# M115C.net
KiCad netlist of a schematic drawn in EAGLE
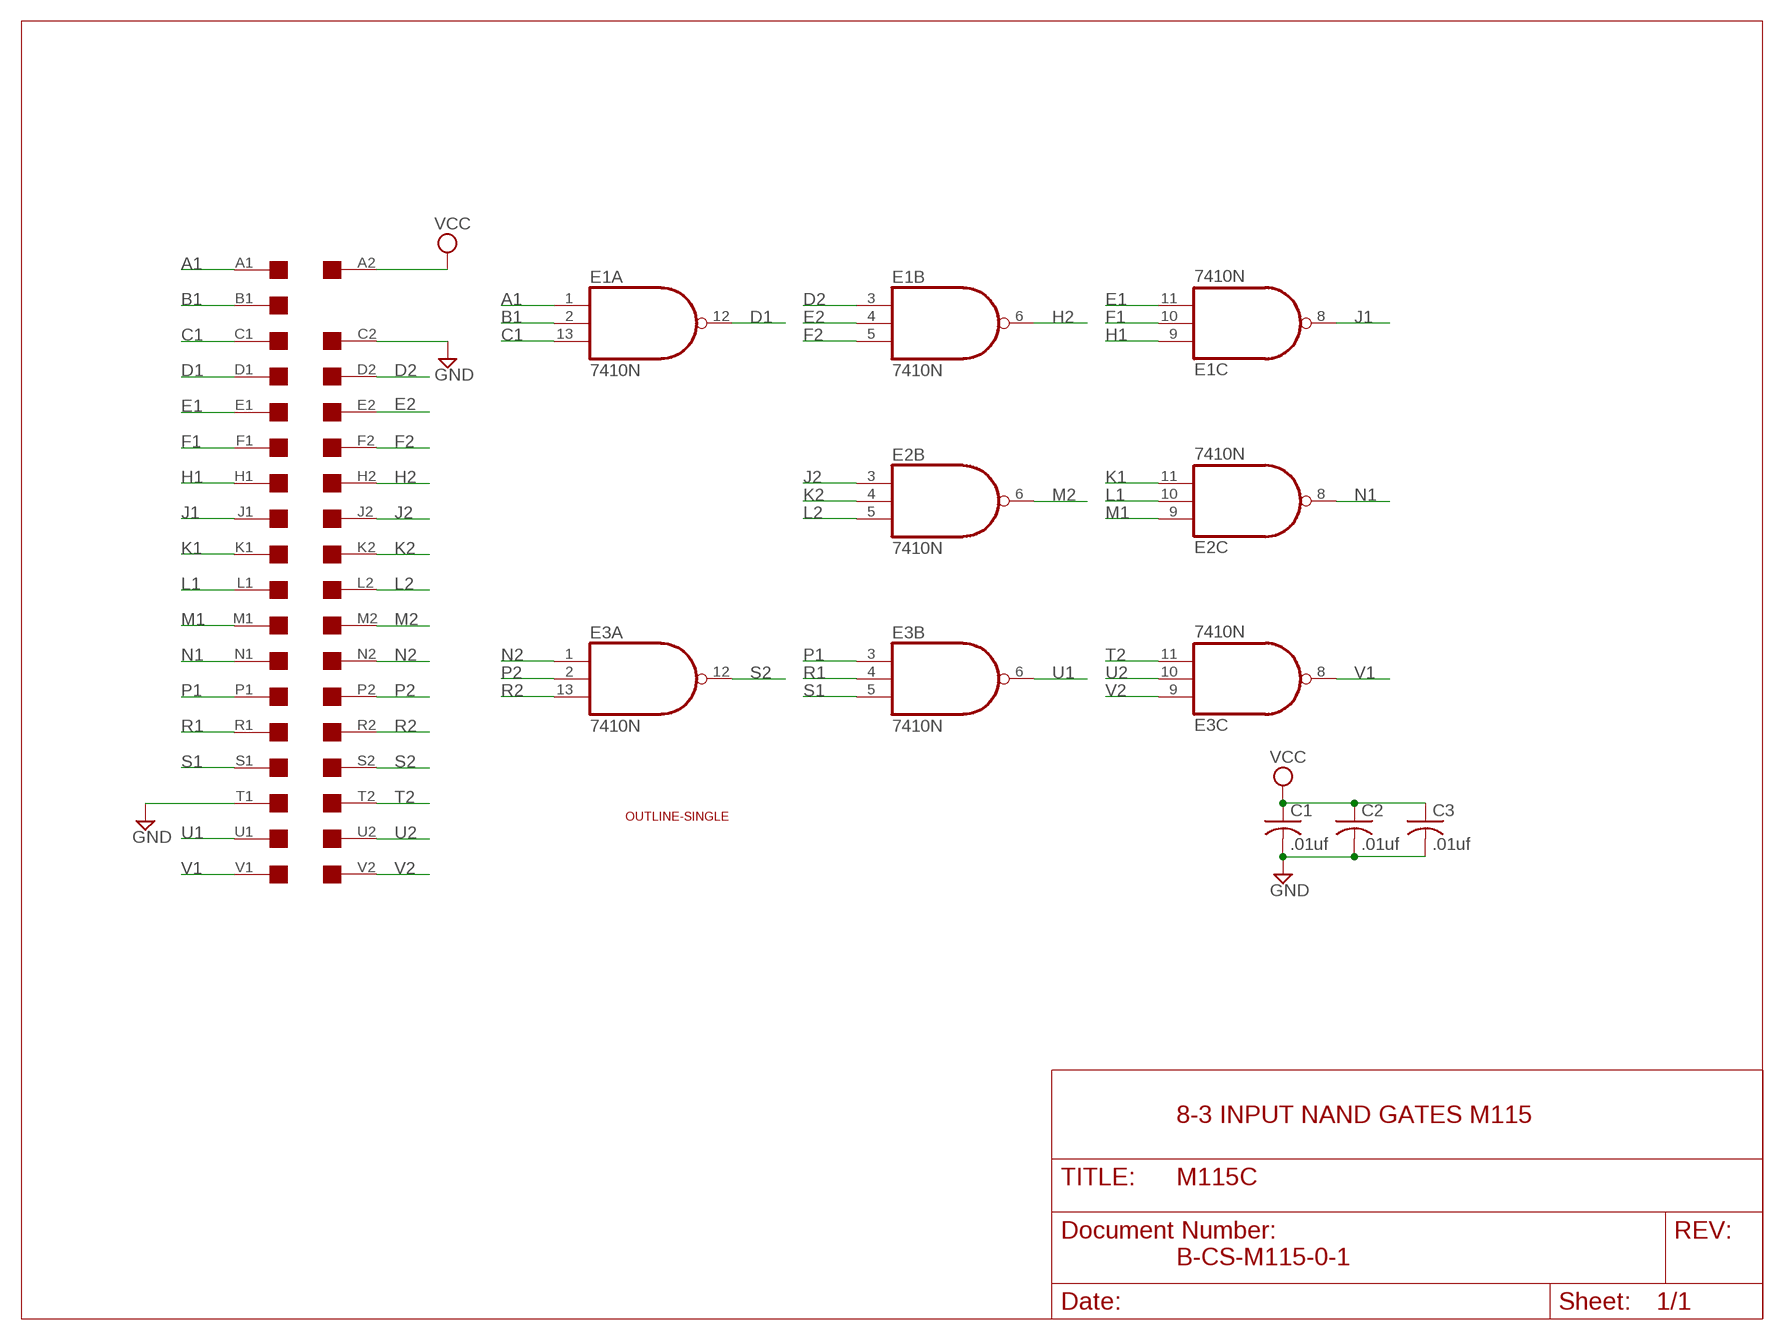
[diagram p0: schematic, sheet 1]

(export (version "E")
  (design (tool "Eeschema 10.0.6"))
  (components
    (comp (ref "C1")
      (value ".01uf")
      (footprint "eagle-import:C050-025X075")
      (libsource (lib "eagle-import") (part "C-US050-025X075"))
    )
    (comp (ref "C2")
      (value ".01uf")
      (footprint "eagle-import:C050-025X075")
      (libsource (lib "eagle-import") (part "C-US050-025X075"))
    )
    (comp (ref "C3")
      (value ".01uf")
      (footprint "eagle-import:C050-025X075")
      (libsource (lib "eagle-import") (part "C-US050-025X075"))
    )
    (comp (ref "E1")
      (value "7410N")
      (footprint "eagle-import:DIL14")
      (libsource (lib "eagle-import") (part "7410N"))
    )
    (comp (ref "E2")
      (value "7410N")
      (footprint "eagle-import:DIL14")
      (libsource (lib "eagle-import") (part "7410N"))
    )
    (comp (ref "E3")
      (value "7410N")
      (footprint "eagle-import:DIL14")
      (libsource (lib "eagle-import") (part "7410N"))
    )
    (comp (ref "U$1")
      (value "SINGLE")
      (footprint "eagle-import:EDGE-CON2")
      (libsource (lib "eagle-import") (part "SINGLE"))
    )
    (comp (ref "U$4")
      (value "OUTLINE-SINGLE")
      (footprint "eagle-import:SINGLE")
      (libsource (lib "eagle-import") (part "OUTLINE-SINGLE"))
    )
  )
  (nets
    (net (code "1") (name "/A1") (class "Default")
      (node (ref "E1") (pin "1") (pinfunction "I0_1") (pintype "input"))
      (node (ref "U$1") (pin "A1") (pinfunction "1_A1") (pintype "bidirectional"))
    )
    (net (code "2") (name "/B1") (class "Default")
      (node (ref "E1") (pin "2") (pinfunction "I1_2") (pintype "input"))
      (node (ref "U$1") (pin "B1") (pinfunction "1_B1") (pintype "bidirectional"))
    )
    (net (code "3") (name "/C1") (class "Default")
      (node (ref "E1") (pin "13") (pinfunction "I2_13") (pintype "input"))
      (node (ref "U$1") (pin "C1") (pinfunction "1_C1") (pintype "bidirectional"))
    )
    (net (code "4") (name "/D1") (class "Default")
      (node (ref "E1") (pin "12") (pinfunction "O_12") (pintype "output"))
      (node (ref "U$1") (pin "D1") (pinfunction "1_D1") (pintype "bidirectional"))
    )
    (net (code "5") (name "/D2") (class "Default")
      (node (ref "E1") (pin "3") (pinfunction "I0_3") (pintype "input"))
      (node (ref "U$1") (pin "D2") (pinfunction "1_D2") (pintype "bidirectional"))
    )
    (net (code "6") (name "/E1") (class "Default")
      (node (ref "E1") (pin "11") (pinfunction "I2_11") (pintype "input"))
      (node (ref "U$1") (pin "E1") (pinfunction "1_E1") (pintype "bidirectional"))
    )
    (net (code "7") (name "/E2") (class "Default")
      (node (ref "E1") (pin "4") (pinfunction "I1_4") (pintype "input"))
      (node (ref "U$1") (pin "E2") (pinfunction "1_E2") (pintype "bidirectional"))
    )
    (net (code "8") (name "/F1") (class "Default")
      (node (ref "E1") (pin "10") (pinfunction "I1_10") (pintype "input"))
      (node (ref "U$1") (pin "F1") (pinfunction "1_F1") (pintype "bidirectional"))
    )
    (net (code "9") (name "/F2") (class "Default")
      (node (ref "E1") (pin "5") (pinfunction "I2_5") (pintype "input"))
      (node (ref "U$1") (pin "F2") (pinfunction "1_F2") (pintype "bidirectional"))
    )
    (net (code "10") (name "/H1") (class "Default")
      (node (ref "E1") (pin "9") (pinfunction "I0_9") (pintype "input"))
      (node (ref "U$1") (pin "H1") (pinfunction "1_H1") (pintype "bidirectional"))
    )
    (net (code "11") (name "/H2") (class "Default")
      (node (ref "E1") (pin "6") (pinfunction "O_6") (pintype "output"))
      (node (ref "U$1") (pin "H2") (pinfunction "1_H2") (pintype "bidirectional"))
    )
    (net (code "12") (name "/J1") (class "Default")
      (node (ref "E1") (pin "8") (pinfunction "O_8") (pintype "output"))
      (node (ref "U$1") (pin "J1") (pinfunction "1_J1") (pintype "bidirectional"))
    )
    (net (code "13") (name "/J2") (class "Default")
      (node (ref "E2") (pin "3") (pinfunction "I0_3") (pintype "input"))
      (node (ref "U$1") (pin "J2") (pinfunction "1_J2") (pintype "bidirectional"))
    )
    (net (code "14") (name "/K1") (class "Default")
      (node (ref "E2") (pin "11") (pinfunction "I2_11") (pintype "input"))
      (node (ref "U$1") (pin "K1") (pinfunction "1_K1") (pintype "bidirectional"))
    )
    (net (code "15") (name "/K2") (class "Default")
      (node (ref "E2") (pin "4") (pinfunction "I1_4") (pintype "input"))
      (node (ref "U$1") (pin "K2") (pinfunction "1_K2") (pintype "bidirectional"))
    )
    (net (code "16") (name "/L1") (class "Default")
      (node (ref "E2") (pin "10") (pinfunction "I1_10") (pintype "input"))
      (node (ref "U$1") (pin "L1") (pinfunction "1_L1") (pintype "bidirectional"))
    )
    (net (code "17") (name "/L2") (class "Default")
      (node (ref "E2") (pin "5") (pinfunction "I2_5") (pintype "input"))
      (node (ref "U$1") (pin "L2") (pinfunction "1_L2") (pintype "bidirectional"))
    )
    (net (code "18") (name "/M1") (class "Default")
      (node (ref "E2") (pin "9") (pinfunction "I0_9") (pintype "input"))
      (node (ref "U$1") (pin "M1") (pinfunction "1_M1") (pintype "bidirectional"))
    )
    (net (code "19") (name "/M2") (class "Default")
      (node (ref "E2") (pin "6") (pinfunction "O_6") (pintype "output"))
      (node (ref "U$1") (pin "M2") (pinfunction "1_M2") (pintype "bidirectional"))
    )
    (net (code "20") (name "/N1") (class "Default")
      (node (ref "E2") (pin "8") (pinfunction "O_8") (pintype "output"))
      (node (ref "U$1") (pin "N1") (pinfunction "1_N1") (pintype "bidirectional"))
    )
    (net (code "21") (name "/N2") (class "Default")
      (node (ref "E3") (pin "1") (pinfunction "I0_1") (pintype "input"))
      (node (ref "U$1") (pin "N2") (pinfunction "1_N2") (pintype "bidirectional"))
    )
    (net (code "22") (name "/P1") (class "Default")
      (node (ref "E3") (pin "3") (pinfunction "I0_3") (pintype "input"))
      (node (ref "U$1") (pin "P1") (pinfunction "1_P1") (pintype "bidirectional"))
    )
    (net (code "23") (name "/P2") (class "Default")
      (node (ref "E3") (pin "2") (pinfunction "I1_2") (pintype "input"))
      (node (ref "U$1") (pin "P2") (pinfunction "1_P2") (pintype "bidirectional"))
    )
    (net (code "24") (name "/R1") (class "Default")
      (node (ref "E3") (pin "4") (pinfunction "I1_4") (pintype "input"))
      (node (ref "U$1") (pin "R1") (pinfunction "1_R1") (pintype "bidirectional"))
    )
    (net (code "25") (name "/R2") (class "Default")
      (node (ref "E3") (pin "13") (pinfunction "I2_13") (pintype "input"))
      (node (ref "U$1") (pin "R2") (pinfunction "1_R2") (pintype "bidirectional"))
    )
    (net (code "26") (name "/S1") (class "Default")
      (node (ref "E3") (pin "5") (pinfunction "I2_5") (pintype "input"))
      (node (ref "U$1") (pin "S1") (pinfunction "1_S1") (pintype "bidirectional"))
    )
    (net (code "27") (name "/S2") (class "Default")
      (node (ref "E3") (pin "12") (pinfunction "O_12") (pintype "output"))
      (node (ref "U$1") (pin "S2") (pinfunction "1_S2") (pintype "bidirectional"))
    )
    (net (code "28") (name "/T2") (class "Default")
      (node (ref "E3") (pin "11") (pinfunction "I2_11") (pintype "input"))
      (node (ref "U$1") (pin "T2") (pinfunction "1_T2") (pintype "bidirectional"))
    )
    (net (code "29") (name "/U1") (class "Default")
      (node (ref "E3") (pin "6") (pinfunction "O_6") (pintype "output"))
      (node (ref "U$1") (pin "U1") (pinfunction "1_U1") (pintype "bidirectional"))
    )
    (net (code "30") (name "/U2") (class "Default")
      (node (ref "E3") (pin "10") (pinfunction "I1_10") (pintype "input"))
      (node (ref "U$1") (pin "U2") (pinfunction "1_U2") (pintype "bidirectional"))
    )
    (net (code "31") (name "/V1") (class "Default")
      (node (ref "E3") (pin "8") (pinfunction "O_8") (pintype "output"))
      (node (ref "U$1") (pin "V1") (pinfunction "1_V1") (pintype "bidirectional"))
    )
    (net (code "32") (name "/V2") (class "Default")
      (node (ref "E3") (pin "9") (pinfunction "I0_9") (pintype "input"))
      (node (ref "U$1") (pin "V2") (pinfunction "1_V2") (pintype "bidirectional"))
    )
    (net (code "33") (name "GND") (class "Default")
      (node (ref "C1") (pin "2") (pinfunction "2_2") (pintype "passive"))
      (node (ref "C2") (pin "2") (pinfunction "2_2") (pintype "passive"))
      (node (ref "C3") (pin "2") (pinfunction "2_2") (pintype "passive"))
      (node (ref "U$1") (pin "C2") (pinfunction "1_C2") (pintype "bidirectional"))
      (node (ref "U$1") (pin "T1") (pinfunction "1_T1") (pintype "bidirectional"))
    )
    (net (code "34") (name "VCC") (class "Default")
      (node (ref "C1") (pin "1") (pinfunction "1_1") (pintype "passive"))
      (node (ref "C2") (pin "1") (pinfunction "1_1") (pintype "passive"))
      (node (ref "C3") (pin "1") (pinfunction "1_1") (pintype "passive"))
      (node (ref "U$1") (pin "A2") (pinfunction "1_A2") (pintype "bidirectional"))
    )
  )
)
